# Capteur_Main_Droite.net
KiCad netlist of a schematic drawn in EasyEDA
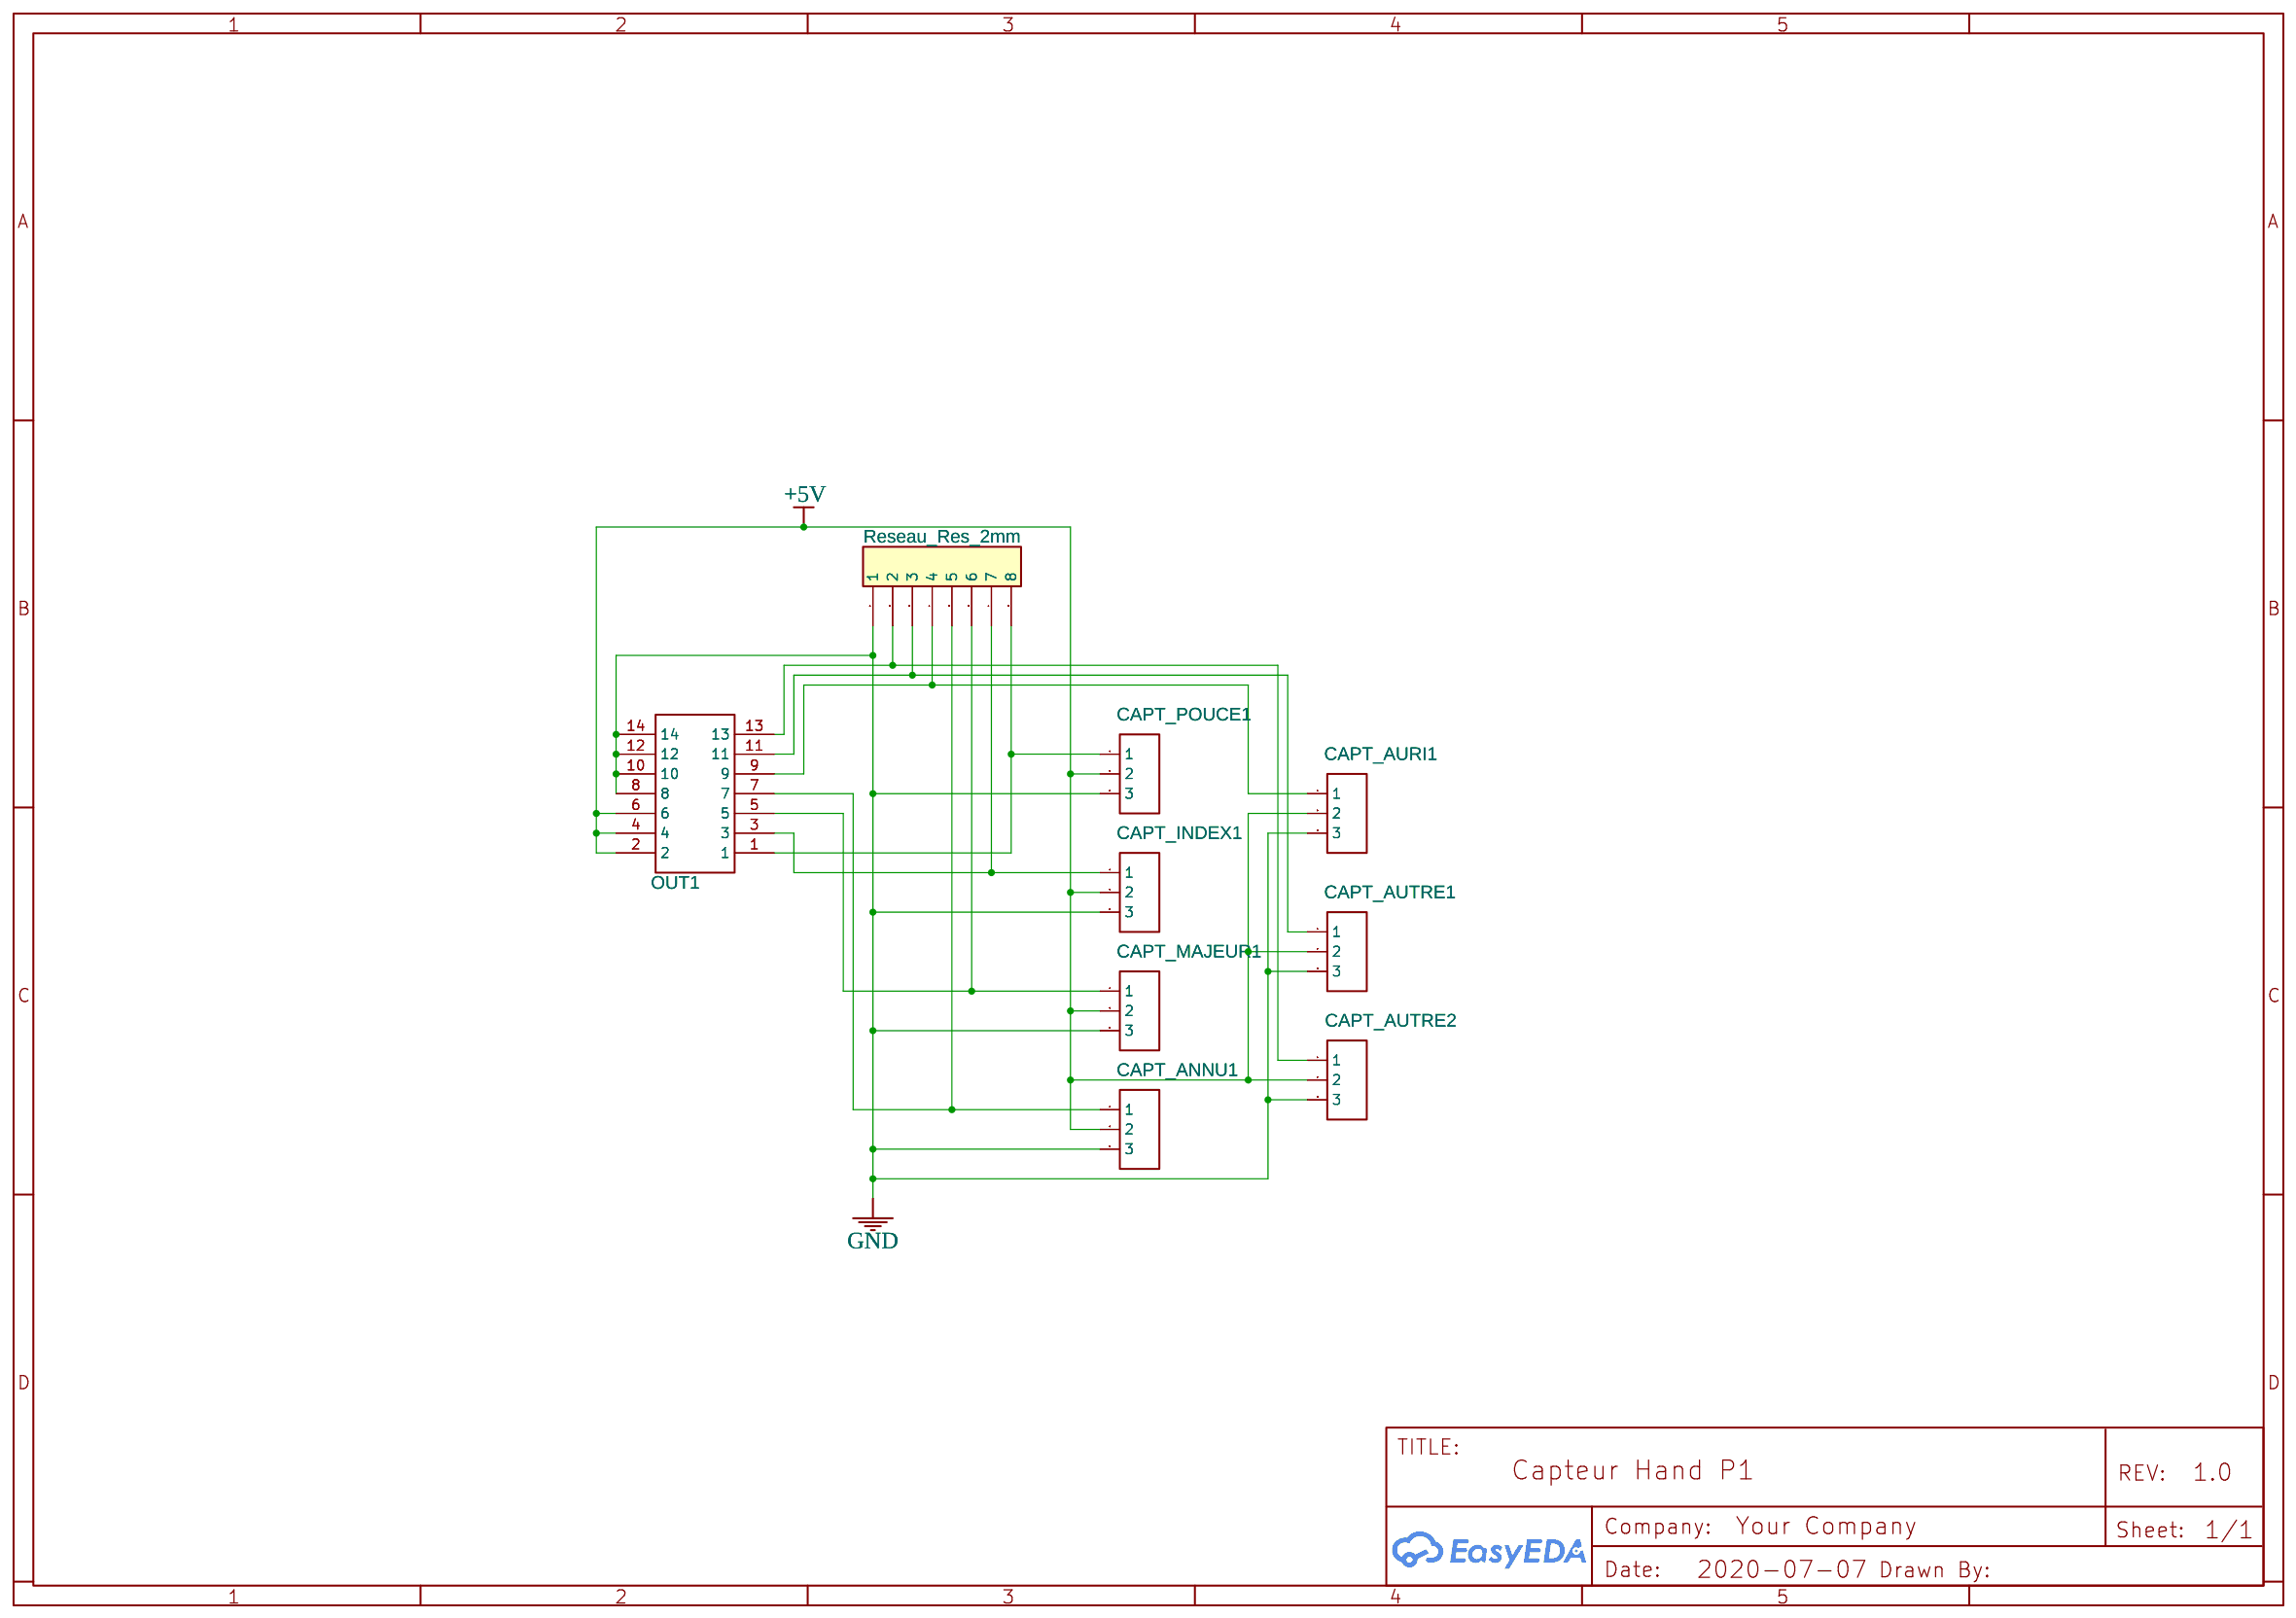
[diagram p0: schematic sheet]

(export (version "E")
  (design (tool "Eeschema 10.0.6"))
  (components
    (comp (ref "CAPT_ANNU1")
      (value "1")
      (fields
        (field (name "BOM_Manufacturer Part") "Header2.54mm 1*3P")
        (field (name "BOM_Supplier Part") "C49257")
      )
      (libsource (lib "") (part "Header-Male-2.54_1x3_1"))
    )
    (comp (ref "CAPT_AURI1")
      (value "1")
      (fields
        (field (name "BOM_Manufacturer Part") "Header2.54mm 1*3P")
        (field (name "BOM_Supplier Part") "C49257")
      )
      (libsource (lib "") (part "Header-Male-2.54_1x3_4"))
    )
    (comp (ref "CAPT_AUTRE1")
      (value "1")
      (fields
        (field (name "BOM_Manufacturer Part") "Header2.54mm 1*3P")
        (field (name "BOM_Supplier Part") "C49257")
      )
      (libsource (lib "") (part "Header-Male-2.54_1x3_2"))
    )
    (comp (ref "CAPT_AUTRE2")
      (value "1")
      (fields
        (field (name "BOM_Manufacturer Part") "Header2.54mm 1*3P")
        (field (name "BOM_Supplier Part") "C49257")
      )
      (libsource (lib "") (part "Header-Male-2.54_1x3_2"))
    )
    (comp (ref "CAPT_INDEX1")
      (value "1")
      (fields
        (field (name "BOM_Manufacturer Part") "Header2.54mm 1*3P")
        (field (name "BOM_Supplier Part") "C49257")
      )
      (libsource (lib "") (part "Header-Male-2.54_1x3"))
    )
    (comp (ref "CAPT_MAJEUR1")
      (value "1")
      (fields
        (field (name "BOM_Manufacturer Part") "Header2.54mm 1*3P")
        (field (name "BOM_Supplier Part") "C49257")
      )
      (libsource (lib "") (part "Header-Male-2.54_1x3_5"))
    )
    (comp (ref "CAPT_POUCE1")
      (value "1")
      (fields
        (field (name "BOM_Manufacturer Part") "Header2.54mm 1*3P")
        (field (name "BOM_Supplier Part") "C49257")
      )
      (libsource (lib "") (part "Header-Male-2.54_1x3_3"))
    )
    (comp (ref "OUT1")
      (value "Horn connector/2.0mm2*7P")
      (fields
        (field (name "BOM_Manufacturer Part") "Horn connector/2.0mm2*7P直简牛")
        (field (name "BOM_Supplier Part") "C29428")
      )
      (libsource (lib "") (part "Horn connector/2.0mm2*7P"))
    )
    (comp (ref "P1") (value "Reseau_Res_2mm") (libsource (lib "") (part "Reseau7R_2mm")))
  )
  (nets
    (net (code "1") (name "+5V") (class "Default")
      (node (ref "CAPT_ANNU1") (pin "2") (pinfunction "2_2") (pintype "input"))
      (node (ref "CAPT_AURI1") (pin "2") (pinfunction "2_2") (pintype "input"))
      (node (ref "CAPT_AUTRE1") (pin "2") (pinfunction "2_2") (pintype "input"))
      (node (ref "CAPT_AUTRE2") (pin "2") (pinfunction "2_2") (pintype "input"))
      (node (ref "CAPT_INDEX1") (pin "2") (pinfunction "2_2") (pintype "input"))
      (node (ref "CAPT_MAJEUR1") (pin "2") (pinfunction "2_2") (pintype "input"))
      (node (ref "CAPT_POUCE1") (pin "2") (pinfunction "2_2") (pintype "input"))
      (node (ref "OUT1") (pin "2") (pinfunction "2_2") (pintype "unspecified"))
      (node (ref "OUT1") (pin "4") (pinfunction "4_4") (pintype "unspecified"))
      (node (ref "OUT1") (pin "6") (pinfunction "6_6") (pintype "unspecified"))
    )
    (net (code "2") (name "GND") (class "Default")
      (node (ref "CAPT_ANNU1") (pin "3") (pinfunction "3_3") (pintype "input"))
      (node (ref "CAPT_AURI1") (pin "3") (pinfunction "3_3") (pintype "input"))
      (node (ref "CAPT_AUTRE1") (pin "3") (pinfunction "3_3") (pintype "input"))
      (node (ref "CAPT_AUTRE2") (pin "3") (pinfunction "3_3") (pintype "input"))
      (node (ref "CAPT_INDEX1") (pin "3") (pinfunction "3_3") (pintype "input"))
      (node (ref "CAPT_MAJEUR1") (pin "3") (pinfunction "3_3") (pintype "input"))
      (node (ref "CAPT_POUCE1") (pin "3") (pinfunction "3_3") (pintype "input"))
      (node (ref "OUT1") (pin "10") (pinfunction "10_10") (pintype "unspecified"))
      (node (ref "OUT1") (pin "12") (pinfunction "12_12") (pintype "unspecified"))
      (node (ref "OUT1") (pin "14") (pinfunction "14_14") (pintype "unspecified"))
      (node (ref "OUT1") (pin "8") (pinfunction "8_8") (pintype "unspecified"))
      (node (ref "P1") (pin "1") (pinfunction "1_1") (pintype "input"))
    )
    (net (code "3") (name "Net-(CAPT_ANNU1-Pad1)") (class "Default")
      (node (ref "CAPT_ANNU1") (pin "1") (pinfunction "1_1") (pintype "input"))
      (node (ref "OUT1") (pin "7") (pinfunction "7_7") (pintype "unspecified"))
      (node (ref "P1") (pin "5") (pinfunction "5_5") (pintype "input"))
    )
    (net (code "4") (name "Net-(CAPT_AURI1-Pad1)") (class "Default")
      (node (ref "CAPT_AURI1") (pin "1") (pinfunction "1_1") (pintype "input"))
      (node (ref "OUT1") (pin "9") (pinfunction "9_9") (pintype "unspecified"))
      (node (ref "P1") (pin "4") (pinfunction "4_4") (pintype "input"))
    )
    (net (code "5") (name "Net-(CAPT_AUTRE1-Pad1)") (class "Default")
      (node (ref "CAPT_AUTRE1") (pin "1") (pinfunction "1_1") (pintype "input"))
      (node (ref "OUT1") (pin "11") (pinfunction "11_11") (pintype "unspecified"))
      (node (ref "P1") (pin "3") (pinfunction "3_3") (pintype "input"))
    )
    (net (code "6") (name "Net-(CAPT_AUTRE2-Pad1)") (class "Default")
      (node (ref "CAPT_AUTRE2") (pin "1") (pinfunction "1_1") (pintype "input"))
      (node (ref "OUT1") (pin "13") (pinfunction "13_13") (pintype "unspecified"))
      (node (ref "P1") (pin "2") (pinfunction "2_2") (pintype "input"))
    )
    (net (code "7") (name "Net-(CAPT_INDEX1-Pad1)") (class "Default")
      (node (ref "CAPT_INDEX1") (pin "1") (pinfunction "1_1") (pintype "input"))
      (node (ref "OUT1") (pin "3") (pinfunction "3_3") (pintype "unspecified"))
      (node (ref "P1") (pin "7") (pinfunction "7_7") (pintype "input"))
    )
    (net (code "8") (name "Net-(CAPT_MAJEUR1-Pad1)") (class "Default")
      (node (ref "CAPT_MAJEUR1") (pin "1") (pinfunction "1_1") (pintype "input"))
      (node (ref "OUT1") (pin "5") (pinfunction "5_5") (pintype "unspecified"))
      (node (ref "P1") (pin "6") (pinfunction "6_6") (pintype "input"))
    )
    (net (code "9") (name "Net-(CAPT_POUCE1-Pad1)") (class "Default")
      (node (ref "CAPT_POUCE1") (pin "1") (pinfunction "1_1") (pintype "input"))
      (node (ref "OUT1") (pin "1") (pinfunction "1_1") (pintype "unspecified"))
      (node (ref "P1") (pin "8") (pinfunction "8_8") (pintype "input"))
    )
  )
)
